# CDCEmu_Logic_stepdown.net
KiCad netlist of a schematic drawn in EAGLE
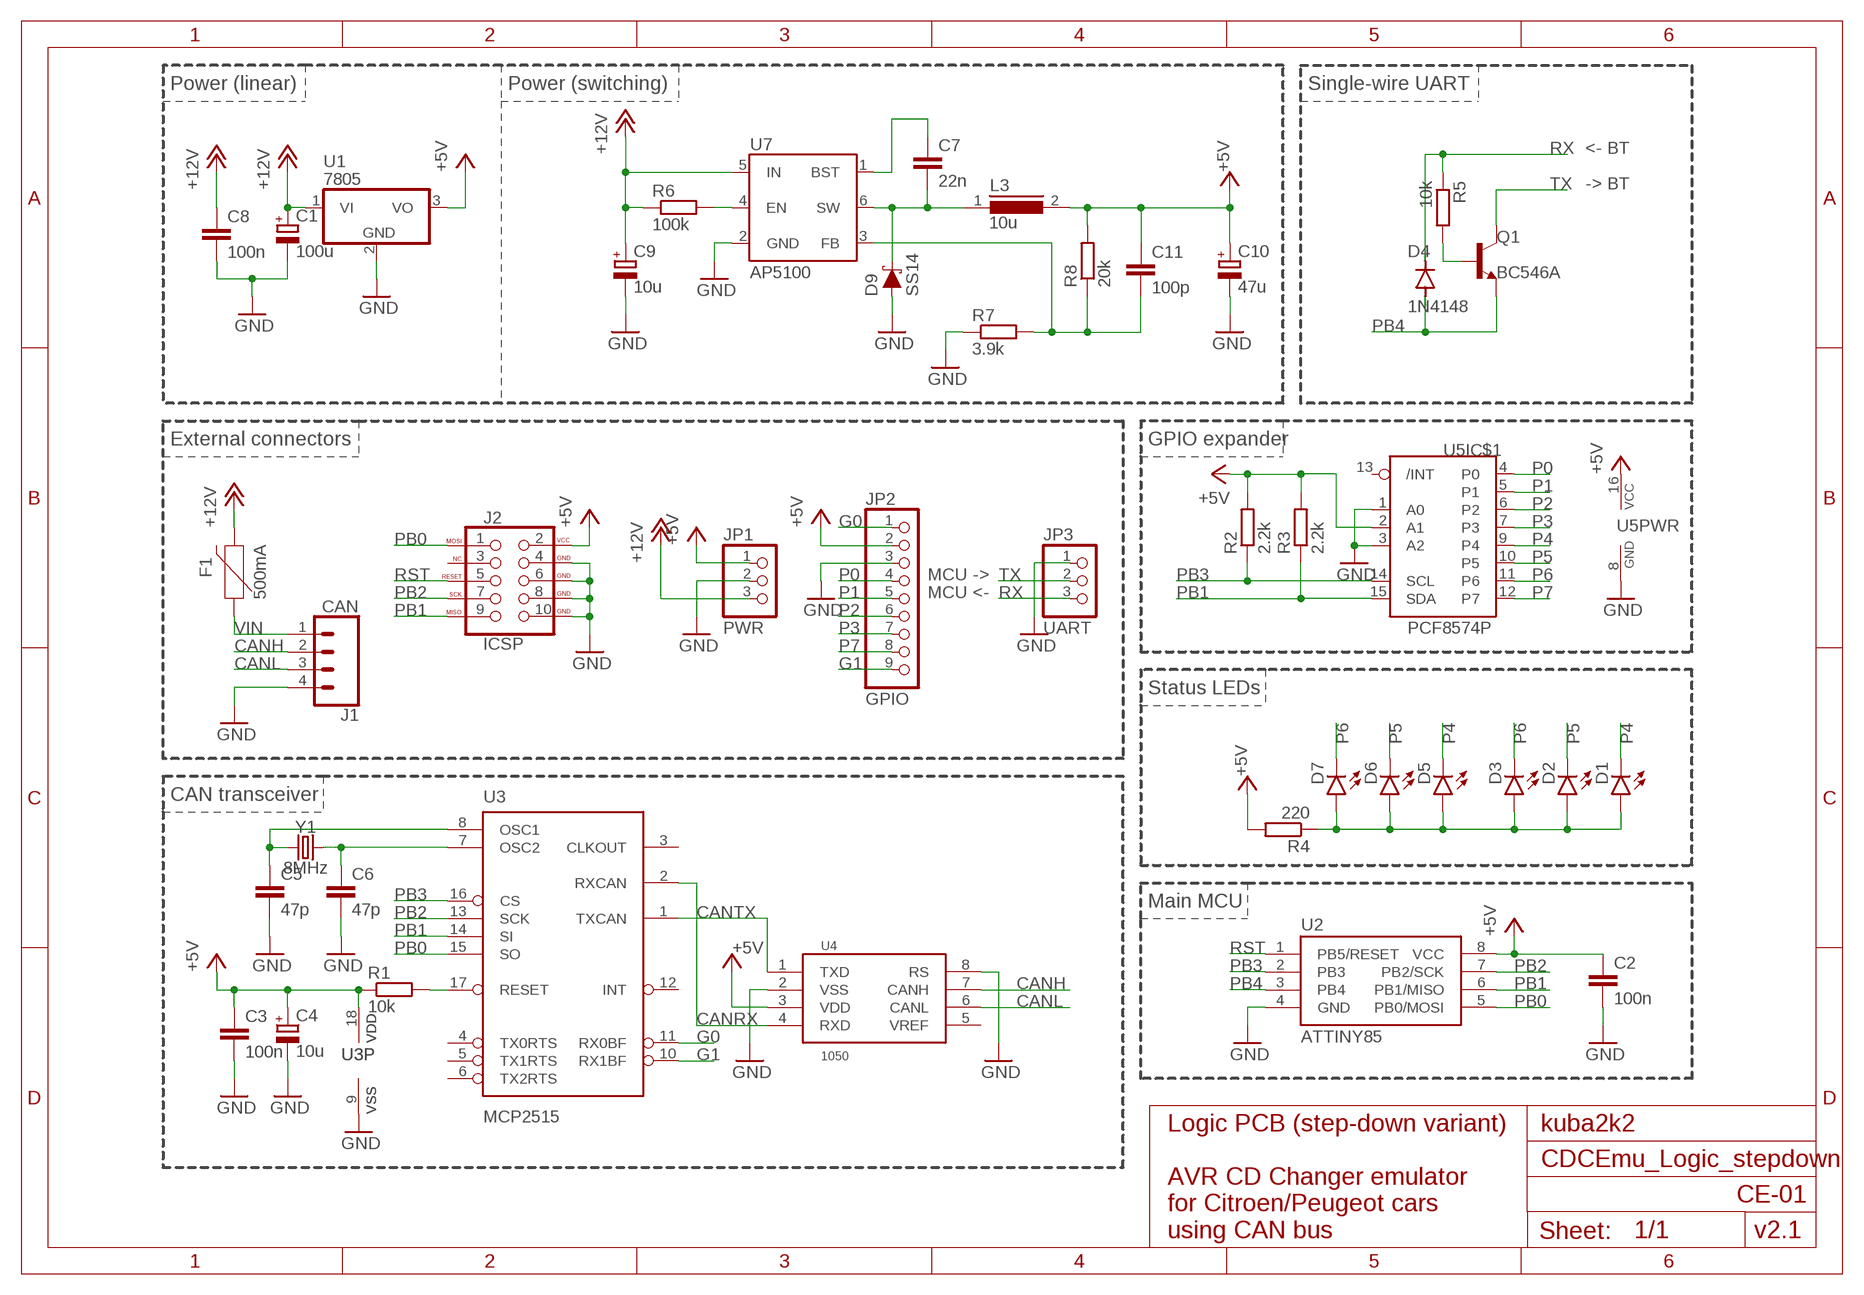
[diagram p0: schematic, sheet 1]

(export (version "E")
  (design (tool "Eeschema 10.0.6"))
  (components
    (comp (ref "C1")
      (value "100u")
      (footprint "eagle-import:E2,5-6")
      (libsource (lib "eagle-import") (part "CPOL-EUE2.5-6"))
    )
    (comp (ref "C2")
      (value "100n")
      (footprint "eagle-import:C050-024X044")
      (libsource (lib "eagle-import") (part "C-EU050-024X044"))
    )
    (comp (ref "C3")
      (value "100n")
      (footprint "eagle-import:C050-024X044")
      (libsource (lib "eagle-import") (part "C-EU050-024X044"))
    )
    (comp (ref "C4")
      (value "10u")
      (footprint "eagle-import:E2,5-6")
      (libsource (lib "eagle-import") (part "CPOL-EUE2.5-6"))
    )
    (comp (ref "C5")
      (value "47p")
      (footprint "eagle-import:C0805")
      (libsource (lib "eagle-import") (part "C-EUC0805"))
    )
    (comp (ref "C6")
      (value "47p")
      (footprint "eagle-import:C0805")
      (libsource (lib "eagle-import") (part "C-EUC0805"))
    )
    (comp (ref "C7")
      (value "22n")
      (footprint "eagle-import:C0805")
      (libsource (lib "eagle-import") (part "C-EUC0805"))
    )
    (comp (ref "C8")
      (value "100n")
      (footprint "eagle-import:C0805")
      (libsource (lib "eagle-import") (part "C-EUC0805"))
    )
    (comp (ref "C9")
      (value "10u")
      (footprint "eagle-import:C2512-POL")
      (libsource (lib "eagle-import") (part "CPOL-EUC2512"))
    )
    (comp (ref "C10")
      (value "47u")
      (footprint "eagle-import:C2512-POL")
      (libsource (lib "eagle-import") (part "CPOL-EUC2512"))
    )
    (comp (ref "C11")
      (value "100p")
      (footprint "eagle-import:C0805")
      (libsource (lib "eagle-import") (part "C-EUC0805"))
    )
    (comp (ref "D1")
      (value "LED3MM")
      (footprint "eagle-import:LED3MM")
      (libsource (lib "eagle-import") (part "LED3MM"))
    )
    (comp (ref "D2")
      (value "LED3MM")
      (footprint "eagle-import:LED3MM")
      (libsource (lib "eagle-import") (part "LED3MM"))
    )
    (comp (ref "D3")
      (value "LED3MM")
      (footprint "eagle-import:LED3MM")
      (libsource (lib "eagle-import") (part "LED3MM"))
    )
    (comp (ref "D4")
      (value "1N4148")
      (footprint "eagle-import:DO35-7")
      (libsource (lib "eagle-import") (part "1N4148DO35-7"))
    )
    (comp (ref "D5")
      (value "LEDCHIP-LED0805")
      (footprint "eagle-import:CHIP-LED0805")
      (libsource (lib "eagle-import") (part "LEDCHIP-LED0805"))
    )
    (comp (ref "D6")
      (value "LEDCHIP-LED0805")
      (footprint "eagle-import:CHIP-LED0805")
      (libsource (lib "eagle-import") (part "LEDCHIP-LED0805"))
    )
    (comp (ref "D7")
      (value "LEDCHIP-LED0805")
      (footprint "eagle-import:CHIP-LED0805")
      (libsource (lib "eagle-import") (part "LEDCHIP-LED0805"))
    )
    (comp (ref "D9")
      (value "SS14")
      (footprint "eagle-import:SMA-DIODE")
      (libsource (lib "eagle-import") (part "DIODE-SCHOTTKY-SS14"))
    )
    (comp (ref "F1")
      (value "500mA")
      (footprint "eagle-import:1812")
      (libsource (lib "eagle-import") (part "PPTC_16V_2.5A"))
    )
    (comp (ref "J1")
      (value "CAN")
      (footprint "eagle-import:JST-4-PTH")
      (libsource (lib "eagle-import") (part "CONN_04JST-PTH"))
    )
    (comp (ref "J2")
      (value "ICSP")
      (footprint "eagle-import:2X5-SHROUDED_LOCK")
      (libsource (lib "eagle-import") (part "AVR_SPI_PROG_5X2LOCK"))
    )
    (comp (ref "JP1")
      (value "PWR")
      (footprint "eagle-import:1X03")
      (libsource (lib "eagle-import") (part "PINHD-1X3"))
    )
    (comp (ref "JP2")
      (value "GPIO")
      (footprint "eagle-import:1X09")
      (libsource (lib "eagle-import") (part "PINHD-1X9"))
    )
    (comp (ref "JP3")
      (value "UART")
      (footprint "eagle-import:1X03")
      (libsource (lib "eagle-import") (part "PINHD-1X3"))
    )
    (comp (ref "L3")
      (value "10u")
      (footprint "eagle-import:L6X6")
      (libsource (lib "eagle-import") (part "INDUCTOR-6X6"))
    )
    (comp (ref "Q1")
      (value "BC546A")
      (footprint "eagle-import:TO92-EBC")
      (libsource (lib "eagle-import") (part "BC546A"))
    )
    (comp (ref "R1")
      (value "10k")
      (footprint "eagle-import:R0805")
      (libsource (lib "eagle-import") (part "R-EU_R0805"))
    )
    (comp (ref "R2")
      (value "2.2k")
      (footprint "eagle-import:0204_7")
      (libsource (lib "eagle-import") (part "R-EU_0204/7"))
    )
    (comp (ref "R3")
      (value "2.2k")
      (footprint "eagle-import:0204_7")
      (libsource (lib "eagle-import") (part "R-EU_0204/7"))
    )
    (comp (ref "R4")
      (value "220")
      (footprint "eagle-import:0204_7")
      (libsource (lib "eagle-import") (part "R-EU_0204/7"))
    )
    (comp (ref "R5")
      (value "10k")
      (footprint "eagle-import:0204_7")
      (libsource (lib "eagle-import") (part "R-EU_0204/7"))
    )
    (comp (ref "R6")
      (value "100k")
      (footprint "eagle-import:R0805")
      (libsource (lib "eagle-import") (part "R-EU_R0805"))
    )
    (comp (ref "R7")
      (value "3.9k")
      (footprint "eagle-import:R0805")
      (libsource (lib "eagle-import") (part "R-EU_R0805"))
    )
    (comp (ref "R8")
      (value "20k")
      (footprint "eagle-import:R0805")
      (libsource (lib "eagle-import") (part "R-EU_R0805"))
    )
    (comp (ref "U1")
      (value "7805")
      (footprint "eagle-import:TO220V")
      (libsource (lib "eagle-import") (part "78TV05"))
    )
    (comp (ref "U2")
      (value "ATTINY85")
      (footprint "eagle-import:PDIP08_300MIL")
      (libsource (lib "eagle-import") (part "ATTINY85P-"))
    )
    (comp (ref "U3")
      (value "MCP2515")
      (footprint "eagle-import:SO18W")
      (libsource (lib "eagle-import") (part "MCP2515(MCP2510)SO"))
    )
    (comp (ref "U4")
      (value "1050")
      (footprint "eagle-import:SO08")
      (libsource (lib "eagle-import") (part "TJA1050"))
    )
    (comp (ref "U5")
      (value "PCF8574P")
      (footprint "eagle-import:DIL16")
      (libsource (lib "eagle-import") (part "PCF8574P"))
    )
    (comp (ref "U7")
      (value "AP5100")
      (footprint "eagle-import:SOT23-6")
      (libsource (lib "eagle-import") (part "AP5100"))
    )
    (comp (ref "Y1")
      (value "8MHz")
      (footprint "eagle-import:HC49U")
      (libsource (lib "eagle-import") (part "CRYSTALPTH-HC49UV"))
    )
  )
  (nets
    (net (code "1") (name "+5V") (class "Default")
      (node (ref "C10") (pin "+") (pinfunction "+_+") (pintype "passive"))
      (node (ref "C11") (pin "1") (pinfunction "1_1") (pintype "passive"))
      (node (ref "C2") (pin "1") (pinfunction "1_1") (pintype "passive"))
      (node (ref "C3") (pin "1") (pinfunction "1_1") (pintype "passive"))
      (node (ref "C4") (pin "+") (pinfunction "+_+") (pintype "passive"))
      (node (ref "J2") (pin "2") (pinfunction "VCC_2") (pintype "power_in"))
      (node (ref "JP1") (pin "1") (pinfunction "1_1") (pintype "passive"))
      (node (ref "JP2") (pin "2") (pinfunction "2_2") (pintype "passive"))
      (node (ref "L3") (pin "2") (pinfunction "2_2") (pintype "passive"))
      (node (ref "R1") (pin "1") (pinfunction "1_1") (pintype "passive"))
      (node (ref "R2") (pin "2") (pinfunction "2_2") (pintype "passive"))
      (node (ref "R3") (pin "2") (pinfunction "2_2") (pintype "passive"))
      (node (ref "R4") (pin "2") (pinfunction "2_2") (pintype "passive"))
      (node (ref "R8") (pin "2") (pinfunction "2_2") (pintype "passive"))
      (node (ref "U1") (pin "3") (pinfunction "VO_3") (pintype "passive"))
      (node (ref "U2") (pin "8") (pinfunction "VCC_8") (pintype "power_in"))
      (node (ref "U3") (pin "18") (pinfunction "VDD_18") (pintype "power_in"))
      (node (ref "U4") (pin "3") (pinfunction "VDD_3") (pintype "power_in"))
      (node (ref "U5") (pin "16") (pinfunction "VCC_16") (pintype "power_in"))
      (node (ref "U5") (pin "2") (pinfunction "A1_2") (pintype "input"))
    )
    (net (code "2") (name "+12V") (class "Default")
      (node (ref "C1") (pin "+") (pinfunction "+_+") (pintype "passive"))
      (node (ref "C8") (pin "1") (pinfunction "1_1") (pintype "passive"))
      (node (ref "C9") (pin "+") (pinfunction "+_+") (pintype "passive"))
      (node (ref "F1") (pin "2") (pinfunction "2_2") (pintype "bidirectional"))
      (node (ref "JP1") (pin "3") (pinfunction "3_3") (pintype "passive"))
      (node (ref "R6") (pin "1") (pinfunction "1_1") (pintype "passive"))
      (node (ref "U1") (pin "1") (pinfunction "VI_1") (pintype "input"))
      (node (ref "U7") (pin "5") (pinfunction "IN_5") (pintype "bidirectional"))
    )
    (net (code "3") (name "/CANH") (class "Default")
      (node (ref "J1") (pin "2") (pinfunction "2_2") (pintype "passive"))
      (node (ref "U4") (pin "7") (pinfunction "CANH_7") (pintype "bidirectional"))
    )
    (net (code "4") (name "/CANL") (class "Default")
      (node (ref "J1") (pin "3") (pinfunction "3_3") (pintype "passive"))
      (node (ref "U4") (pin "6") (pinfunction "CANL_6") (pintype "bidirectional"))
    )
    (net (code "5") (name "/CANRX") (class "Default")
      (node (ref "U3") (pin "2") (pinfunction "RXCAN_2") (pintype "input"))
      (node (ref "U4") (pin "4") (pinfunction "RXD_4") (pintype "output"))
    )
    (net (code "6") (name "/CANTX") (class "Default")
      (node (ref "U3") (pin "1") (pinfunction "TXCAN_1") (pintype "output"))
      (node (ref "U4") (pin "1") (pinfunction "TXD_1") (pintype "input"))
    )
    (net (code "7") (name "/G0") (class "Default")
      (node (ref "JP2") (pin "1") (pinfunction "1_1") (pintype "passive"))
      (node (ref "U3") (pin "11") (pinfunction "RX0BF_11") (pintype "output"))
    )
    (net (code "8") (name "/G1") (class "Default")
      (node (ref "JP2") (pin "9") (pinfunction "9_9") (pintype "passive"))
      (node (ref "U3") (pin "10") (pinfunction "RX1BF_10") (pintype "output"))
    )
    (net (code "9") (name "/P0") (class "Default")
      (node (ref "JP2") (pin "4") (pinfunction "4_4") (pintype "passive"))
      (node (ref "U5") (pin "4") (pinfunction "P0_4") (pintype "bidirectional"))
    )
    (net (code "10") (name "/P1") (class "Default")
      (node (ref "JP2") (pin "5") (pinfunction "5_5") (pintype "passive"))
      (node (ref "U5") (pin "5") (pinfunction "P1_5") (pintype "bidirectional"))
    )
    (net (code "11") (name "/P2") (class "Default")
      (node (ref "JP2") (pin "6") (pinfunction "6_6") (pintype "passive"))
      (node (ref "U5") (pin "6") (pinfunction "P2_6") (pintype "bidirectional"))
    )
    (net (code "12") (name "/P3") (class "Default")
      (node (ref "JP2") (pin "7") (pinfunction "7_7") (pintype "passive"))
      (node (ref "U5") (pin "7") (pinfunction "P3_7") (pintype "bidirectional"))
    )
    (net (code "13") (name "/P4") (class "Default")
      (node (ref "D1") (pin "K") (pinfunction "C_K") (pintype "passive"))
      (node (ref "D5") (pin "C") (pinfunction "C_C") (pintype "passive"))
      (node (ref "U5") (pin "9") (pinfunction "P4_9") (pintype "bidirectional"))
    )
    (net (code "14") (name "/P5") (class "Default")
      (node (ref "D2") (pin "K") (pinfunction "C_K") (pintype "passive"))
      (node (ref "D6") (pin "C") (pinfunction "C_C") (pintype "passive"))
      (node (ref "U5") (pin "10") (pinfunction "P5_10") (pintype "bidirectional"))
    )
    (net (code "15") (name "/P6") (class "Default")
      (node (ref "D3") (pin "K") (pinfunction "C_K") (pintype "passive"))
      (node (ref "D7") (pin "C") (pinfunction "C_C") (pintype "passive"))
      (node (ref "U5") (pin "11") (pinfunction "P6_11") (pintype "bidirectional"))
    )
    (net (code "16") (name "/P7") (class "Default")
      (node (ref "JP2") (pin "8") (pinfunction "8_8") (pintype "passive"))
      (node (ref "U5") (pin "12") (pinfunction "P7_12") (pintype "bidirectional"))
    )
    (net (code "17") (name "/PB0") (class "Default")
      (node (ref "J2") (pin "1") (pinfunction "MOSI_1") (pintype "passive"))
      (node (ref "U2") (pin "5") (pinfunction "PB0/MOSI_5") (pintype "bidirectional"))
      (node (ref "U3") (pin "15") (pinfunction "SO_15") (pintype "output"))
    )
    (net (code "18") (name "/PB1") (class "Default")
      (node (ref "J2") (pin "9") (pinfunction "MISO_9") (pintype "passive"))
      (node (ref "R3") (pin "1") (pinfunction "1_1") (pintype "passive"))
      (node (ref "U2") (pin "6") (pinfunction "PB1/MISO_6") (pintype "bidirectional"))
      (node (ref "U3") (pin "14") (pinfunction "SI_14") (pintype "input"))
      (node (ref "U5") (pin "15") (pinfunction "SDA_15") (pintype "bidirectional"))
    )
    (net (code "19") (name "/PB2") (class "Default")
      (node (ref "J2") (pin "7") (pinfunction "SCK_7") (pintype "passive"))
      (node (ref "U2") (pin "7") (pinfunction "PB2/SCK_7") (pintype "bidirectional"))
      (node (ref "U3") (pin "13") (pinfunction "SCK_13") (pintype "input"))
    )
    (net (code "20") (name "/PB3") (class "Default")
      (node (ref "R2") (pin "1") (pinfunction "1_1") (pintype "passive"))
      (node (ref "U2") (pin "2") (pinfunction "PB3_2") (pintype "bidirectional"))
      (node (ref "U3") (pin "16") (pinfunction "CS_16") (pintype "input"))
      (node (ref "U5") (pin "14") (pinfunction "SCL_14") (pintype "input"))
    )
    (net (code "21") (name "/PB4") (class "Default")
      (node (ref "D4") (pin "A") (pinfunction "A_A") (pintype "passive"))
      (node (ref "Q1") (pin "E") (pinfunction "E_E") (pintype "passive"))
      (node (ref "U2") (pin "3") (pinfunction "PB4_3") (pintype "bidirectional"))
    )
    (net (code "22") (name "/RST") (class "Default")
      (node (ref "J2") (pin "5") (pinfunction "RESET_5") (pintype "passive"))
      (node (ref "U2") (pin "1") (pinfunction "PB5/RESET_1") (pintype "bidirectional"))
    )
    (net (code "23") (name "/RX") (class "Default")
      (node (ref "D4") (pin "C") (pinfunction "C_C") (pintype "passive"))
      (node (ref "JP3") (pin "3") (pinfunction "3_3") (pintype "passive"))
      (node (ref "R5") (pin "1") (pinfunction "1_1") (pintype "passive"))
    )
    (net (code "24") (name "/TX") (class "Default")
      (node (ref "JP3") (pin "2") (pinfunction "2_2") (pintype "passive"))
      (node (ref "Q1") (pin "C") (pinfunction "C_C") (pintype "passive"))
    )
    (net (code "25") (name "/VIN") (class "Default")
      (node (ref "F1") (pin "1") (pinfunction "1_1") (pintype "bidirectional"))
      (node (ref "J1") (pin "1") (pinfunction "1_1") (pintype "passive"))
    )
    (net (code "26") (name "GND") (class "Default")
      (node (ref "C1") (pin "-") (pinfunction "-_-") (pintype "passive"))
      (node (ref "C10") (pin "-") (pinfunction "-_-") (pintype "passive"))
      (node (ref "C2") (pin "2") (pinfunction "2_2") (pintype "passive"))
      (node (ref "C3") (pin "2") (pinfunction "2_2") (pintype "passive"))
      (node (ref "C4") (pin "-") (pinfunction "-_-") (pintype "passive"))
      (node (ref "C5") (pin "2") (pinfunction "2_2") (pintype "passive"))
      (node (ref "C6") (pin "2") (pinfunction "2_2") (pintype "passive"))
      (node (ref "C8") (pin "2") (pinfunction "2_2") (pintype "passive"))
      (node (ref "C9") (pin "-") (pinfunction "-_-") (pintype "passive"))
      (node (ref "D9") (pin "A") (pinfunction "A_A") (pintype "passive"))
      (node (ref "J1") (pin "4") (pinfunction "4_4") (pintype "passive"))
      (node (ref "J2") (pin "10") (pinfunction "GND_10") (pintype "power_in"))
      (node (ref "J2") (pin "4") (pinfunction "GND_4") (pintype "power_in"))
      (node (ref "J2") (pin "6") (pinfunction "GND_6") (pintype "power_in"))
      (node (ref "J2") (pin "8") (pinfunction "GND_8") (pintype "power_in"))
      (node (ref "JP1") (pin "2") (pinfunction "2_2") (pintype "passive"))
      (node (ref "JP2") (pin "3") (pinfunction "3_3") (pintype "passive"))
      (node (ref "JP3") (pin "1") (pinfunction "1_1") (pintype "passive"))
      (node (ref "R7") (pin "1") (pinfunction "1_1") (pintype "passive"))
      (node (ref "U1") (pin "2") (pinfunction "GND_2") (pintype "passive"))
      (node (ref "U2") (pin "4") (pinfunction "GND_4") (pintype "power_in"))
      (node (ref "U3") (pin "9") (pinfunction "VSS_9") (pintype "power_in"))
      (node (ref "U4") (pin "2") (pinfunction "VSS_2") (pintype "power_in"))
      (node (ref "U4") (pin "8") (pinfunction "RS_8") (pintype "input"))
      (node (ref "U5") (pin "1") (pinfunction "A0_1") (pintype "input"))
      (node (ref "U5") (pin "3") (pinfunction "A2_3") (pintype "input"))
      (node (ref "U5") (pin "8") (pinfunction "GND_8") (pintype "power_in"))
      (node (ref "U7") (pin "2") (pinfunction "GND_2") (pintype "bidirectional"))
    )
    (net (code "27") (name "Net-(D1-PadA)") (class "Default")
      (node (ref "D1") (pin "A") (pinfunction "A_A") (pintype "passive"))
      (node (ref "D2") (pin "A") (pinfunction "A_A") (pintype "passive"))
      (node (ref "D3") (pin "A") (pinfunction "A_A") (pintype "passive"))
      (node (ref "D5") (pin "A") (pinfunction "A_A") (pintype "passive"))
      (node (ref "D6") (pin "A") (pinfunction "A_A") (pintype "passive"))
      (node (ref "D7") (pin "A") (pinfunction "A_A") (pintype "passive"))
      (node (ref "R4") (pin "1") (pinfunction "1_1") (pintype "passive"))
    )
    (net (code "28") (name "Net-(Q1-PadB)") (class "Default")
      (node (ref "Q1") (pin "B") (pinfunction "B_B") (pintype "passive"))
      (node (ref "R5") (pin "2") (pinfunction "2_2") (pintype "passive"))
    )
    (net (code "29") (name "Net-(U3A-OSC1)") (class "Default")
      (node (ref "C5") (pin "1") (pinfunction "1_1") (pintype "passive"))
      (node (ref "U3") (pin "8") (pinfunction "OSC1_8") (pintype "input"))
      (node (ref "Y1") (pin "1") (pinfunction "1_1") (pintype "passive"))
    )
    (net (code "30") (name "Net-(U3A-OSC2)") (class "Default")
      (node (ref "C6") (pin "1") (pinfunction "1_1") (pintype "passive"))
      (node (ref "U3") (pin "7") (pinfunction "OSC2_7") (pintype "output"))
      (node (ref "Y1") (pin "2") (pinfunction "2_2") (pintype "passive"))
    )
    (net (code "31") (name "Net-(U3A-RESET)") (class "Default")
      (node (ref "R1") (pin "2") (pinfunction "2_2") (pintype "passive"))
      (node (ref "U3") (pin "17") (pinfunction "RESET_17") (pintype "input"))
    )
    (net (code "32") (name "Net-(U7-BST)") (class "Default")
      (node (ref "C7") (pin "1") (pinfunction "1_1") (pintype "passive"))
      (node (ref "U7") (pin "1") (pinfunction "BST_1") (pintype "bidirectional"))
    )
    (net (code "33") (name "Net-(U7-EN)") (class "Default")
      (node (ref "R6") (pin "2") (pinfunction "2_2") (pintype "passive"))
      (node (ref "U7") (pin "4") (pinfunction "EN_4") (pintype "bidirectional"))
    )
    (net (code "34") (name "Net-(U7-FB)") (class "Default")
      (node (ref "C11") (pin "2") (pinfunction "2_2") (pintype "passive"))
      (node (ref "R7") (pin "2") (pinfunction "2_2") (pintype "passive"))
      (node (ref "R8") (pin "1") (pinfunction "1_1") (pintype "passive"))
      (node (ref "U7") (pin "3") (pinfunction "FB_3") (pintype "bidirectional"))
    )
    (net (code "35") (name "Net-(U7-SW)") (class "Default")
      (node (ref "C7") (pin "2") (pinfunction "2_2") (pintype "passive"))
      (node (ref "D9") (pin "C") (pinfunction "C_C") (pintype "passive"))
      (node (ref "L3") (pin "1") (pinfunction "1_1") (pintype "passive"))
      (node (ref "U7") (pin "6") (pinfunction "SW_6") (pintype "bidirectional"))
    )
    (net (code "36") (name "unconnected-(J2-NC-Pad3)") (class "Default")
      (node (ref "J2") (pin "3") (pinfunction "NC_3") (pintype "no_connect"))
    )
    (net (code "37") (name "unconnected-(U3A-CLKOUT-Pad3)") (class "Default")
      (node (ref "U3") (pin "3") (pinfunction "CLKOUT_3") (pintype "output"))
    )
    (net (code "38") (name "unconnected-(U3A-INT-Pad12)") (class "Default")
      (node (ref "U3") (pin "12") (pinfunction "INT_12") (pintype "output"))
    )
    (net (code "39") (name "unconnected-(U3A-TX0RTS-Pad4)") (class "Default")
      (node (ref "U3") (pin "4") (pinfunction "TX0RTS_4") (pintype "input"))
    )
    (net (code "40") (name "unconnected-(U3A-TX1RTS-Pad5)") (class "Default")
      (node (ref "U3") (pin "5") (pinfunction "TX1RTS_5") (pintype "input"))
    )
    (net (code "41") (name "unconnected-(U3A-TX2RTS-Pad6)") (class "Default")
      (node (ref "U3") (pin "6") (pinfunction "TX2RTS_6") (pintype "input"))
    )
    (net (code "42") (name "unconnected-(U4-VREF-Pad5)") (class "Default")
      (node (ref "U4") (pin "5") (pinfunction "VREF_5") (pintype "passive"))
    )
    (net (code "43") (name "unconnected-(U5A-{slash}INT-Pad13)") (class "Default")
      (node (ref "U5") (pin "13") (pinfunction "/INT_13") (pintype "output"))
    )
  )
)
